# Server_QSPI_Flash_EEPROM.net
KiCad netlist of a schematic drawn in Altium Designer
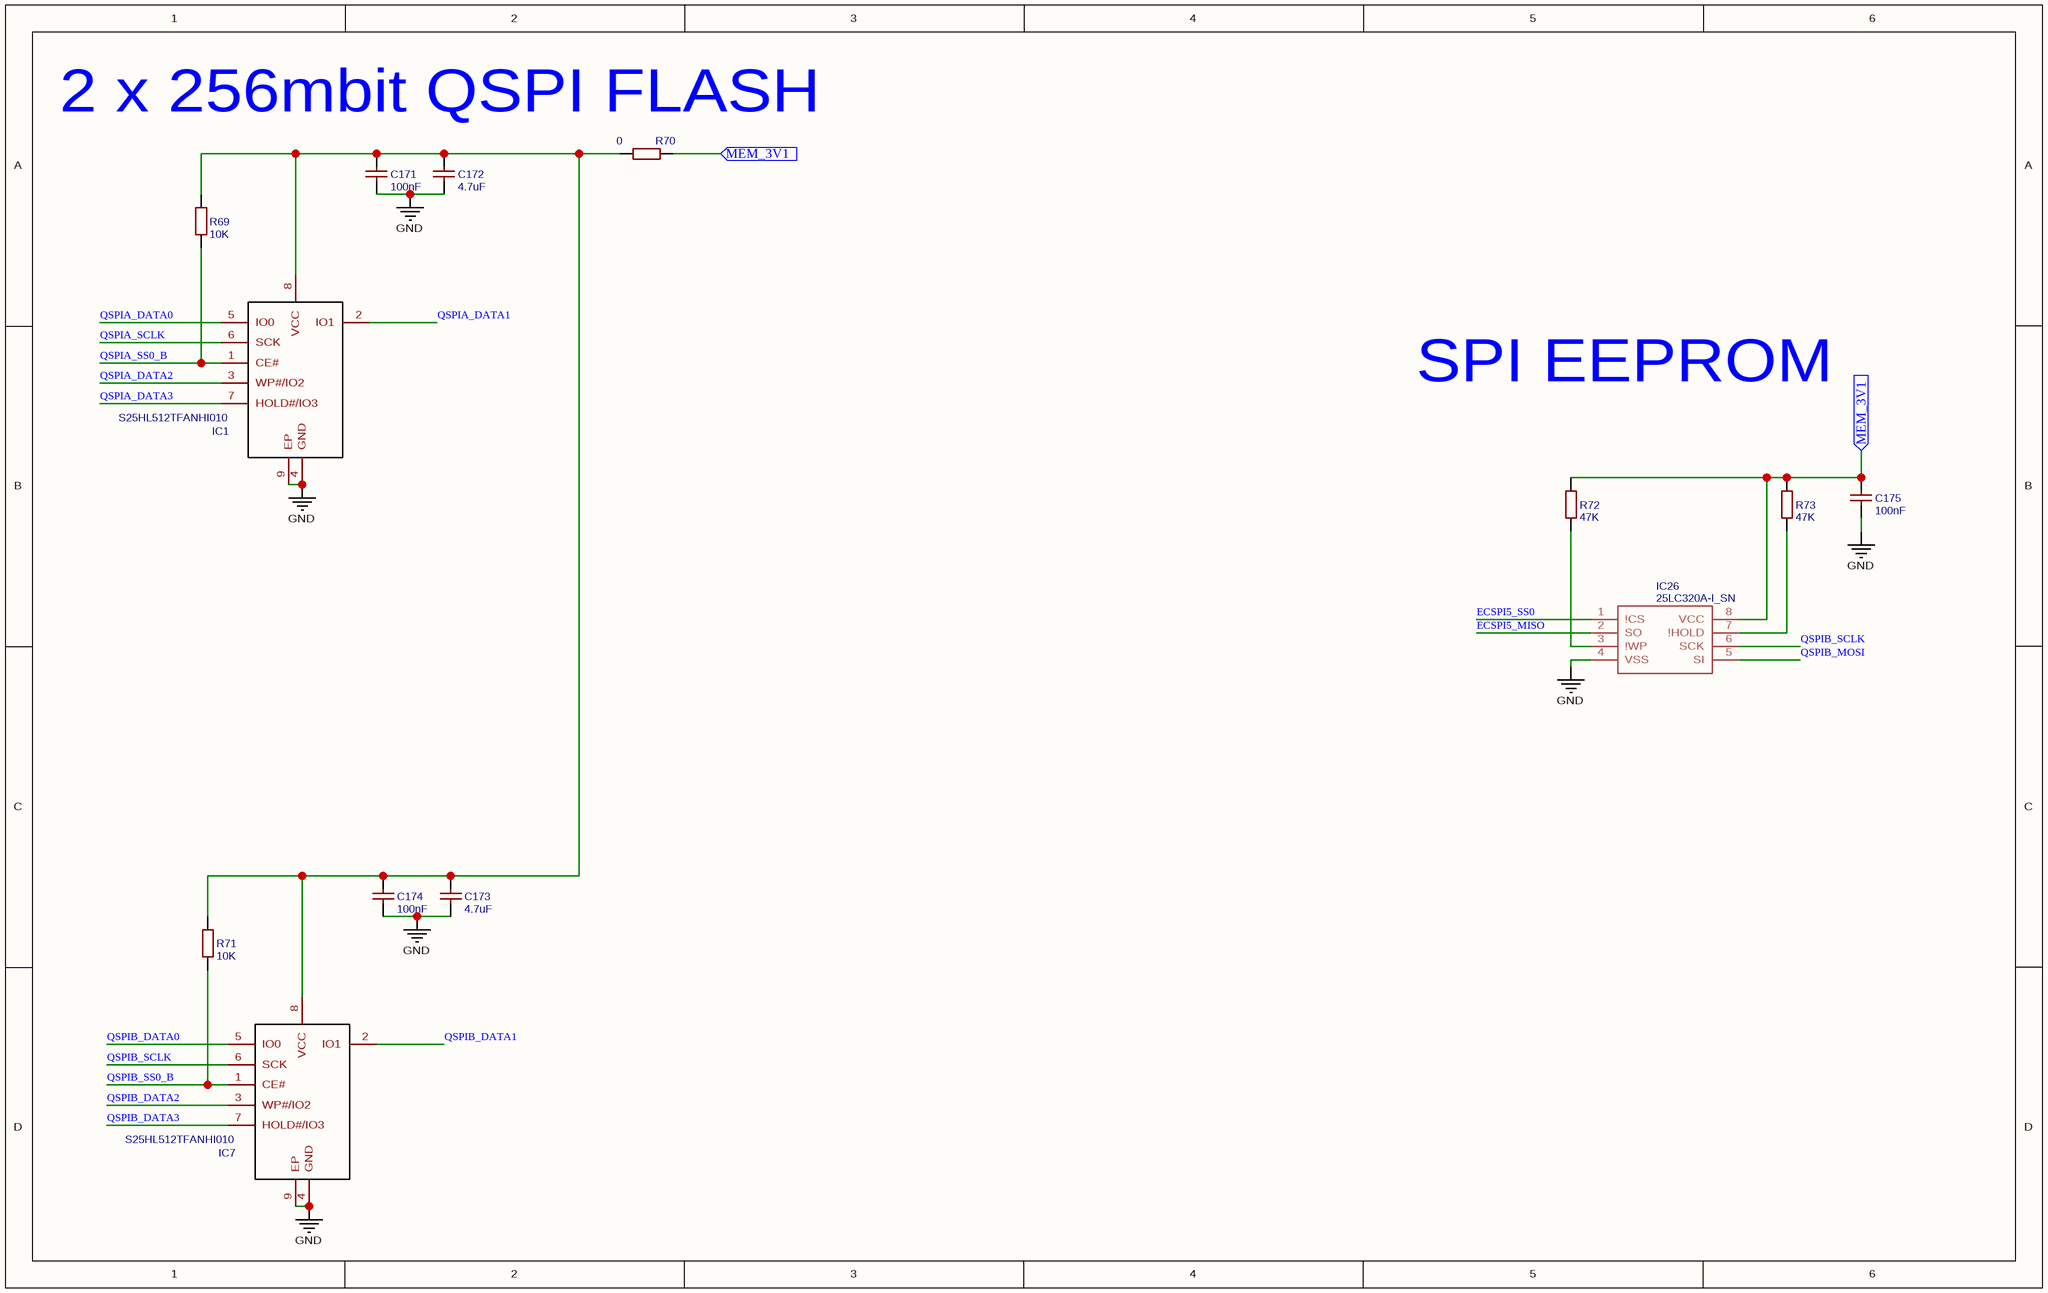
[diagram p0: Server QSPI Flash & EEPROM.schdoc]

(export (version "E")
  (design (tool "Eeschema 10.0.6"))
  (components
    (comp (ref "C171")
      (value "100nF")
      (fields
        (field (name "BOM_MANUFACTURER PART") "CC0805KRX7R9BB104")
        (field (name "BOM_SUPPLIER PART") "C49678")
      )
      (libsource (lib "altium-import") (part "root_1_100nF_"))
    )
    (comp (ref "C172")
      (value "4.7uF")
      (fields
        (field (name "BOM_MANUFACTURER PART") "CL05A475MP5NRNC")
        (field (name "BOM_SUPPLIER PART") "C23733")
      )
      (libsource (lib "altium-import") (part "root_1_4.7uF_"))
    )
    (comp (ref "C173")
      (value "4.7uF")
      (fields
        (field (name "BOM_MANUFACTURER PART") "CL05A475MP5NRNC")
        (field (name "BOM_SUPPLIER PART") "C23733")
      )
      (libsource (lib "altium-import") (part "root_1_4.7uF_"))
    )
    (comp (ref "C174")
      (value "100nF")
      (fields
        (field (name "BOM_MANUFACTURER PART") "CC0805KRX7R9BB104")
        (field (name "BOM_SUPPLIER PART") "C49678")
      )
      (libsource (lib "altium-import") (part "root_1_100nF_"))
    )
    (comp (ref "C175")
      (value "100nF")
      (fields
        (field (name "BOM_MANUFACTURER PART") "CC0805KRX7R9BB104")
        (field (name "BOM_SUPPLIER PART") "C49678")
      )
      (libsource (lib "altium-import") (part "root_1_100nF_"))
    )
    (comp (ref "IC1")
      (value "S25HL512TFANHI010")
      (fields (field (name "CONTRIBUTOR") "Ke'Ondrae_Mell"))
      (libsource (lib "altium-import") (part "root_0_S25HL512TFANHI010_"))
    )
    (comp (ref "IC7")
      (value "S25HL512TFANHI010")
      (fields (field (name "CONTRIBUTOR") "Ke'Ondrae_Mell"))
      (libsource (lib "altium-import") (part "root_0_S25HL512TFANHI010_"))
    )
    (comp (ref "IC26")
      (value "25LC320A-I_SN")
      (fields (field (name "CONTRIBUTOR") "Ke'Ondrae_Mell"))
      (libsource (lib "altium-import") (part "root_0_25LC320A-I_SN_"))
    )
    (comp (ref "R69")
      (value "10K")
      (fields
        (field (name "BOM_MANUFACTURER PART") "0402WGF1002TCE")
        (field (name "BOM_SUPPLIER PART") "C25744")
      )
      (libsource (lib "altium-import") (part "root_1_10K_"))
    )
    (comp (ref "R70")
      (value "0")
      (fields
        (field (name "BOM_MANUFACTURER PART") "RK73Z1ETTP")
        (field (name "BOM_SUPPLIER PART") "C131359")
      )
      (libsource (lib "altium-import") (part "root_0_0_"))
    )
    (comp (ref "R71")
      (value "10K")
      (fields
        (field (name "BOM_MANUFACTURER PART") "0402WGF1002TCE")
        (field (name "BOM_SUPPLIER PART") "C25744")
      )
      (libsource (lib "altium-import") (part "root_1_10K_"))
    )
    (comp (ref "R72")
      (value "47K")
      (fields
        (field (name "BOM_MANUFACTURER PART") "0805W8F4702T5E")
        (field (name "BOM_SUPPLIER PART") "C17713")
      )
      (libsource (lib "altium-import") (part "root_1_47K_"))
    )
    (comp (ref "R73")
      (value "47K")
      (fields
        (field (name "BOM_MANUFACTURER PART") "0805W8F4702T5E")
        (field (name "BOM_SUPPLIER PART") "C17713")
      )
      (libsource (lib "altium-import") (part "root_1_47K_"))
    )
  )
  (nets
    (net (code "1") (name "/ECSPI5_MISO") (class "Default")
      (node (ref "IC26") (pin "2") (pinfunction "SO_2") (pintype "passive"))
    )
    (net (code "2") (name "/ECSPI5_SS0") (class "Default")
      (node (ref "IC26") (pin "1") (pinfunction "!CS_1") (pintype "passive"))
    )
    (net (code "3") (name "/MEM_3V1") (class "Default")
      (node (ref "C175") (pin "2") (pinfunction "2_2") (pintype "passive"))
      (node (ref "IC26") (pin "8") (pinfunction "VCC_8") (pintype "passive"))
      (node (ref "R70") (pin "2") (pinfunction "2_2") (pintype "passive"))
      (node (ref "R72") (pin "2") (pinfunction "2_2") (pintype "passive"))
      (node (ref "R73") (pin "2") (pinfunction "2_2") (pintype "passive"))
    )
    (net (code "4") (name "/QSPIA_DATA0") (class "Default")
      (node (ref "IC1") (pin "5") (pinfunction "IO0_5") (pintype "passive"))
    )
    (net (code "5") (name "/QSPIA_DATA1") (class "Default")
      (node (ref "IC1") (pin "2") (pinfunction "IO1_2") (pintype "passive"))
    )
    (net (code "6") (name "/QSPIA_DATA2") (class "Default")
      (node (ref "IC1") (pin "3") (pinfunction "WP#/IO2_3") (pintype "passive"))
    )
    (net (code "7") (name "/QSPIA_DATA3") (class "Default")
      (node (ref "IC1") (pin "7") (pinfunction "HOLD#/IO3_7") (pintype "passive"))
    )
    (net (code "8") (name "/QSPIA_SCLK") (class "Default")
      (node (ref "IC1") (pin "6") (pinfunction "SCK_6") (pintype "passive"))
    )
    (net (code "9") (name "/QSPIA_SS0_B") (class "Default")
      (node (ref "IC1") (pin "1") (pinfunction "CE#_1") (pintype "passive"))
      (node (ref "R69") (pin "1") (pinfunction "1_1") (pintype "passive"))
    )
    (net (code "10") (name "/QSPIB_DATA0") (class "Default")
      (node (ref "IC7") (pin "5") (pinfunction "IO0_5") (pintype "passive"))
    )
    (net (code "11") (name "/QSPIB_DATA1") (class "Default")
      (node (ref "IC7") (pin "2") (pinfunction "IO1_2") (pintype "passive"))
    )
    (net (code "12") (name "/QSPIB_DATA2") (class "Default")
      (node (ref "IC7") (pin "3") (pinfunction "WP#/IO2_3") (pintype "passive"))
    )
    (net (code "13") (name "/QSPIB_DATA3") (class "Default")
      (node (ref "IC7") (pin "7") (pinfunction "HOLD#/IO3_7") (pintype "passive"))
    )
    (net (code "14") (name "/QSPIB_MOSI") (class "Default")
      (node (ref "IC26") (pin "5") (pinfunction "SI_5") (pintype "passive"))
    )
    (net (code "15") (name "/QSPIB_SCLK") (class "Default")
      (node (ref "IC26") (pin "6") (pinfunction "SCK_6") (pintype "passive"))
      (node (ref "IC7") (pin "6") (pinfunction "SCK_6") (pintype "passive"))
    )
    (net (code "16") (name "/QSPIB_SS0_B") (class "Default")
      (node (ref "IC7") (pin "1") (pinfunction "CE#_1") (pintype "passive"))
      (node (ref "R71") (pin "1") (pinfunction "1_1") (pintype "passive"))
    )
    (net (code "17") (name "GND") (class "Default")
      (node (ref "C171") (pin "1") (pinfunction "1_1") (pintype "passive"))
      (node (ref "C172") (pin "1") (pinfunction "1_1") (pintype "passive"))
      (node (ref "C173") (pin "1") (pinfunction "1_1") (pintype "passive"))
      (node (ref "C174") (pin "1") (pinfunction "1_1") (pintype "passive"))
      (node (ref "C175") (pin "1") (pinfunction "1_1") (pintype "passive"))
      (node (ref "IC1") (pin "4") (pinfunction "GND_4") (pintype "passive"))
      (node (ref "IC1") (pin "9") (pinfunction "EP_9") (pintype "passive"))
      (node (ref "IC26") (pin "4") (pinfunction "VSS_4") (pintype "passive"))
      (node (ref "IC7") (pin "4") (pinfunction "GND_4") (pintype "passive"))
      (node (ref "IC7") (pin "9") (pinfunction "EP_9") (pintype "passive"))
    )
    (net (code "18") (name "Net-(IC1-VCC)") (class "Default")
      (node (ref "C171") (pin "2") (pinfunction "2_2") (pintype "passive"))
      (node (ref "C172") (pin "2") (pinfunction "2_2") (pintype "passive"))
      (node (ref "C173") (pin "2") (pinfunction "2_2") (pintype "passive"))
      (node (ref "C174") (pin "2") (pinfunction "2_2") (pintype "passive"))
      (node (ref "IC1") (pin "8") (pinfunction "VCC_8") (pintype "passive"))
      (node (ref "IC7") (pin "8") (pinfunction "VCC_8") (pintype "passive"))
      (node (ref "R69") (pin "2") (pinfunction "2_2") (pintype "passive"))
      (node (ref "R70") (pin "1") (pinfunction "1_1") (pintype "passive"))
      (node (ref "R71") (pin "2") (pinfunction "2_2") (pintype "passive"))
    )
    (net (code "19") (name "Net-(IC26-!HOLD)") (class "Default")
      (node (ref "IC26") (pin "7") (pinfunction "!HOLD_7") (pintype "passive"))
      (node (ref "R73") (pin "1") (pinfunction "1_1") (pintype "passive"))
    )
    (net (code "20") (name "Net-(IC26-!WP)") (class "Default")
      (node (ref "IC26") (pin "3") (pinfunction "!WP_3") (pintype "passive"))
      (node (ref "R72") (pin "1") (pinfunction "1_1") (pintype "passive"))
    )
  )
)
